# CH32V203C8T6-R0.net
KiCad netlist of a schematic drawn in Altium Designer
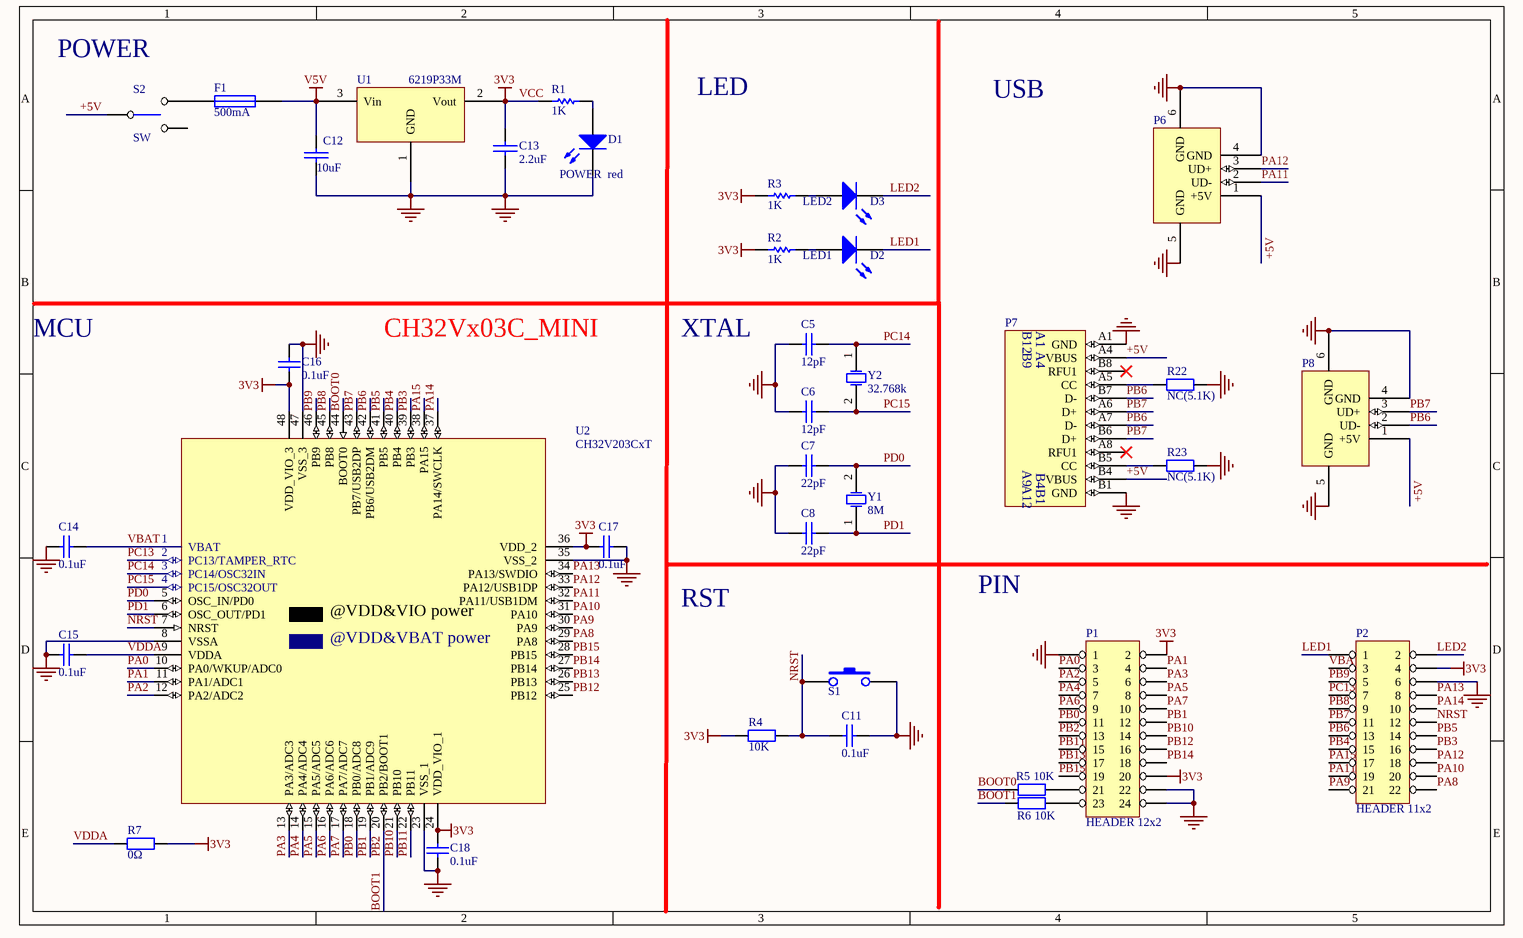
[diagram p0: CH32V203C8T6-R0.SchDoc]

(export (version "E")
  (design (tool "Eeschema 10.0.6"))
  (components
    (comp (ref "C5")
      (value "12pF")
      (footprint "0603_C")
      (description "Capacitor")
      (fields (field (name "PUBLISHER") "Altium Limited"))
      (libsource (lib "*") (part "Cap"))
    )
    (comp (ref "C6")
      (value "12pF")
      (footprint "0603_C")
      (description "Capacitor")
      (fields (field (name "PUBLISHER") "Altium Limited"))
      (libsource (lib "*") (part "Cap"))
    )
    (comp (ref "C7")
      (value "22pF")
      (footprint "0603_C")
      (description "Capacitor")
      (fields (field (name "PUBLISHER") "Altium Limited"))
      (libsource (lib "*") (part "Cap"))
    )
    (comp (ref "C8")
      (value "22pF")
      (footprint "0603_C")
      (description "Capacitor")
      (fields (field (name "PUBLISHER") "Altium Limited"))
      (libsource (lib "*") (part "Cap"))
    )
    (comp (ref "C11")
      (value "0.1uF")
      (footprint "0603_C")
      (description "Capacitor")
      (fields (field (name "PUBLISHER") "Altium Limited"))
      (libsource (lib "*") (part "Cap"))
    )
    (comp (ref "C12")
      (value "10uF")
      (footprint "3216_C")
      (description "Capacitor")
      (libsource (lib "*") (part "CAP"))
    )
    (comp (ref "C13")
      (value "2.2uF")
      (footprint "0603_C")
      (description "Capacitor")
      (libsource (lib "*") (part "CAP"))
    )
    (comp (ref "C14")
      (value "0.1uF")
      (footprint "0603_C")
      (description "Capacitor")
      (fields (field (name "PUBLISHER") "Altium Limited"))
      (libsource (lib "*") (part "Cap"))
    )
    (comp (ref "C15")
      (value "0.1uF")
      (footprint "0603_C")
      (description "Capacitor")
      (fields (field (name "PUBLISHER") "Altium Limited"))
      (libsource (lib "*") (part "Cap"))
    )
    (comp (ref "C16")
      (value "0.1uF")
      (footprint "0603_C")
      (description "Capacitor")
      (fields (field (name "PUBLISHER") "Altium Limited"))
      (libsource (lib "*") (part "Cap"))
    )
    (comp (ref "C17")
      (value "0.1uF")
      (footprint "0603_C")
      (description "Capacitor")
      (fields (field (name "PUBLISHER") "Altium Limited"))
      (libsource (lib "*") (part "Cap"))
    )
    (comp (ref "C18")
      (value "0.1uF")
      (footprint "0603_C")
      (description "Capacitor")
      (fields (field (name "PUBLISHER") "Altium Limited"))
      (libsource (lib "*") (part "Cap"))
    )
    (comp (ref "D1")
      (value "POWER  red")
      (footprint "0603+")
      (description "Typical INFRARED GaAs LED")
      (fields (field (name "PUBLISHER") "Altium Limited"))
      (libsource (lib "*") (part "LED0"))
    )
    (comp (ref "D2")
      (value "LED1")
      (footprint "0603+")
      (description "Typical INFRARED GaAs LED")
      (fields (field (name "PUBLISHER") "Altium Limited"))
      (libsource (lib "*") (part "LED0"))
    )
    (comp (ref "D3")
      (value "LED2")
      (footprint "0603+")
      (description "Typical INFRARED GaAs LED")
      (fields (field (name "PUBLISHER") "Altium Limited"))
      (libsource (lib "*") (part "LED0"))
    )
    (comp (ref "F1")
      (value "500mA")
      (footprint "0603")
      (description "Fuse")
      (libsource (lib "*") (part "FUSE1"))
    )
    (comp (ref "P1")
      (value "HEADER 12x2")
      (footprint "MYPCB:IDC24-2.54MM")
      (description "Header, 12-Pin, Dual row")
      (libsource (lib "wch_sch_others") (part "HEADER 12x2"))
    )
    (comp (ref "P2")
      (value "HEADER 11x2")
      (footprint "MYPCB:IDC22-2.54MM")
      (description "Header, 11-Pin, Dual row")
      (libsource (lib "wch_sch_others") (part "HEADER 11x2"))
    )
    (comp (ref "P6")
      (value "USB_A")
      (footprint "USBAF")
      (description "USB Port")
      (libsource (lib "*") (part "USB"))
    )
    (comp (ref "P7")
      (value "TYPE-C")
      (footprint "TYPE-C-Receptacle-2.0")
      (libsource (lib "*") (part "TYPE-C1"))
    )
    (comp (ref "P8")
      (value "USB_A")
      (footprint "USBAF")
      (description "USB Port")
      (libsource (lib "*") (part "USB"))
    )
    (comp (ref "R1")
      (value "1K")
      (footprint "0603")
      (description "Semiconductor Resistor")
      (fields (field (name "PUBLISHER") "Altium Limited"))
      (libsource (lib "*") (part "Res Semi"))
    )
    (comp (ref "R2")
      (value "1K")
      (footprint "0603")
      (description "Semiconductor Resistor")
      (fields (field (name "PUBLISHER") "Altium Limited"))
      (libsource (lib "*") (part "Res Semi"))
    )
    (comp (ref "R3")
      (value "1K")
      (footprint "0603")
      (description "Semiconductor Resistor")
      (fields (field (name "PUBLISHER") "Altium Limited"))
      (libsource (lib "*") (part "Res Semi"))
    )
    (comp (ref "R4")
      (value "10K")
      (footprint "0603")
      (description "Resistor")
      (fields (field (name "PUBLISHER") "Altium Limited"))
      (libsource (lib "*") (part "Res2"))
    )
    (comp (ref "R5")
      (value "10K")
      (footprint "0603")
      (description "Resistor")
      (fields (field (name "PUBLISHER") "Altium Limited"))
      (libsource (lib "") (part "Res2_1"))
    )
    (comp (ref "R6")
      (value "10K")
      (footprint "0603")
      (description "Resistor")
      (fields (field (name "PUBLISHER") "Altium Limited"))
      (libsource (lib "") (part "Res2_1"))
    )
    (comp (ref "R7")
      (value "0Ω")
      (footprint "0603")
      (description "Resistor")
      (fields (field (name "PUBLISHER") "Altium Limited"))
      (libsource (lib "*") (part "Res2"))
    )
    (comp (ref "R22")
      (value "NC(5.1K)")
      (footprint "0603")
      (description "Resistor")
      (libsource (lib "Miscellaneous Devices") (part "Res2"))
    )
    (comp (ref "R23")
      (value "NC(5.1K)")
      (footprint "0603")
      (description "Resistor")
      (libsource (lib "Miscellaneous Devices") (part "Res2"))
    )
    (comp (ref "S1") (value "KEY") (footprint "贴片按键") (libsource (lib "*") (part "KEY")))
    (comp (ref "S2") (value "SW") (footprint "KEY2") (libsource (lib "*") (part "SW")))
    (comp (ref "U1")
      (value "6219P33M")
      (footprint "SOT-23")
      (libsource (lib "wch_sch_others") (part "6219P33M"))
    )
    (comp (ref "U2")
      (value "CH32V203CxT")
      (footprint "LQFP48")
      (description "RISC-V LMD-MCU, 144MHz, 2*USB FS, CAN")
      (libsource (lib "CHXXX") (part "CH32V203CxT"))
    )
    (comp (ref "Y1")
      (value "8M")
      (footprint "XT_AT49")
      (description "Crystal Oscillator")
      (fields (field (name "PUBLISHER") "Altium Limited"))
      (libsource (lib "*") (part "XTAL"))
    )
    (comp (ref "Y2")
      (value "32.768k")
      (footprint "FC-135")
      (description "Crystal Oscillator")
      (fields (field (name "PUBLISHER") "Altium Limited"))
      (libsource (lib "*") (part "XTAL"))
    )
  )
  (nets
    (net (code "1") (name "/+5V") (class "Default")
      (node (ref "P6") (pin "1") (pinfunction "+5V_1") (pintype "power_in"))
      (node (ref "P7") (pin "A4") (pinfunction "VBUS_A4") (pintype "bidirectional"))
      (node (ref "P7") (pin "B4") (pinfunction "VBUS_B4") (pintype "bidirectional"))
      (node (ref "P8") (pin "1") (pinfunction "+5V_1") (pintype "power_in"))
      (node (ref "S2") (pin "1") (pinfunction "1_1") (pintype "passive"))
    )
    (net (code "3") (name "/BOOT0") (class "Default")
      (node (ref "R5") (pin "1") (pinfunction "1_1") (pintype "passive"))
      (node (ref "U2") (pin "44") (pinfunction "BOOT0_44") (pintype "input"))
    )
    (net (code "4") (name "/BOOT1") (class "Default")
      (node (ref "P1") (pin "13") (pinfunction "13_13") (pintype "passive"))
      (node (ref "R6") (pin "1") (pinfunction "1_1") (pintype "passive"))
      (node (ref "U2") (pin "20") (pinfunction "PB2/BOOT1_20") (pintype "bidirectional"))
    )
    (net (code "5") (name "/LED1") (class "Default")
      (node (ref "D2") (pin "2") (pinfunction "K_2") (pintype "passive"))
      (node (ref "P2") (pin "1") (pinfunction "1_1") (pintype "passive"))
    )
    (net (code "6") (name "/LED2") (class "Default")
      (node (ref "D3") (pin "2") (pinfunction "K_2") (pintype "passive"))
      (node (ref "P2") (pin "2") (pinfunction "2_2") (pintype "passive"))
    )
    (net (code "7") (name "/NRST") (class "Default")
      (node (ref "C11") (pin "2") (pinfunction "2_2") (pintype "passive"))
      (node (ref "P2") (pin "12") (pinfunction "12_12") (pintype "passive"))
      (node (ref "R4") (pin "1") (pinfunction "1_1") (pintype "passive"))
      (node (ref "S1") (pin "1") (pinfunction "1_1") (pintype "passive"))
      (node (ref "U2") (pin "7") (pinfunction "NRST_7") (pintype "input"))
    )
    (net (code "8") (name "/PA0") (class "Default")
      (node (ref "P1") (pin "3") (pinfunction "3_3") (pintype "passive"))
      (node (ref "U2") (pin "10") (pinfunction "PA0/WKUP/ADC0_10") (pintype "bidirectional"))
    )
    (net (code "9") (name "/PA1") (class "Default")
      (node (ref "P1") (pin "4") (pinfunction "4_4") (pintype "passive"))
      (node (ref "U2") (pin "11") (pinfunction "PA1/ADC1_11") (pintype "bidirectional"))
    )
    (net (code "10") (name "/PA2") (class "Default")
      (node (ref "P1") (pin "5") (pinfunction "5_5") (pintype "passive"))
      (node (ref "U2") (pin "12") (pinfunction "PA2/ADC2_12") (pintype "bidirectional"))
    )
    (net (code "11") (name "/PA3") (class "Default")
      (node (ref "P1") (pin "6") (pinfunction "6_6") (pintype "passive"))
      (node (ref "U2") (pin "13") (pinfunction "PA3/ADC3_13") (pintype "bidirectional"))
    )
    (net (code "12") (name "/PA4") (class "Default")
      (node (ref "P1") (pin "7") (pinfunction "7_7") (pintype "passive"))
      (node (ref "U2") (pin "14") (pinfunction "PA4/ADC4_14") (pintype "bidirectional"))
    )
    (net (code "13") (name "/PA5") (class "Default")
      (node (ref "P1") (pin "8") (pinfunction "8_8") (pintype "passive"))
      (node (ref "U2") (pin "15") (pinfunction "PA5/ADC5_15") (pintype "bidirectional"))
    )
    (net (code "14") (name "/PA6") (class "Default")
      (node (ref "P1") (pin "9") (pinfunction "9_9") (pintype "passive"))
      (node (ref "U2") (pin "16") (pinfunction "PA6/ADC6_16") (pintype "bidirectional"))
    )
    (net (code "15") (name "/PA7") (class "Default")
      (node (ref "P1") (pin "10") (pinfunction "10_10") (pintype "passive"))
      (node (ref "U2") (pin "17") (pinfunction "PA7/ADC7_17") (pintype "bidirectional"))
    )
    (net (code "16") (name "/PA8") (class "Default")
      (node (ref "P2") (pin "22") (pinfunction "22_22") (pintype "passive"))
      (node (ref "U2") (pin "29") (pinfunction "PA8_29") (pintype "bidirectional"))
    )
    (net (code "17") (name "/PA9") (class "Default")
      (node (ref "P2") (pin "21") (pinfunction "21_21") (pintype "passive"))
      (node (ref "U2") (pin "30") (pinfunction "PA9_30") (pintype "bidirectional"))
    )
    (net (code "18") (name "/PA10") (class "Default")
      (node (ref "P2") (pin "20") (pinfunction "20_20") (pintype "passive"))
      (node (ref "U2") (pin "31") (pinfunction "PA10_31") (pintype "bidirectional"))
    )
    (net (code "19") (name "/PA11") (class "Default")
      (node (ref "P2") (pin "19") (pinfunction "19_19") (pintype "passive"))
      (node (ref "P6") (pin "2") (pinfunction "UD-_2") (pintype "bidirectional"))
      (node (ref "U2") (pin "32") (pinfunction "PA11/USB1DM_32") (pintype "bidirectional"))
    )
    (net (code "20") (name "/PA12") (class "Default")
      (node (ref "P2") (pin "18") (pinfunction "18_18") (pintype "passive"))
      (node (ref "P6") (pin "3") (pinfunction "UD+_3") (pintype "bidirectional"))
      (node (ref "U2") (pin "33") (pinfunction "PA12/USB1DP_33") (pintype "bidirectional"))
    )
    (net (code "21") (name "/PA13") (class "Default")
      (node (ref "P2") (pin "8") (pinfunction "8_8") (pintype "passive"))
      (node (ref "U2") (pin "34") (pinfunction "PA13/SWDIO_34") (pintype "bidirectional"))
    )
    (net (code "22") (name "/PA14") (class "Default")
      (node (ref "P2") (pin "10") (pinfunction "10_10") (pintype "passive"))
      (node (ref "U2") (pin "37") (pinfunction "PA14/SWCLK_37") (pintype "bidirectional"))
    )
    (net (code "23") (name "/PA15") (class "Default")
      (node (ref "P2") (pin "17") (pinfunction "17_17") (pintype "passive"))
      (node (ref "U2") (pin "38") (pinfunction "PA15_38") (pintype "bidirectional"))
    )
    (net (code "24") (name "/PB0") (class "Default")
      (node (ref "P1") (pin "11") (pinfunction "11_11") (pintype "passive"))
      (node (ref "U2") (pin "18") (pinfunction "PB0/ADC8_18") (pintype "bidirectional"))
    )
    (net (code "25") (name "/PB1") (class "Default")
      (node (ref "P1") (pin "12") (pinfunction "12_12") (pintype "passive"))
      (node (ref "U2") (pin "19") (pinfunction "PB1/ADC9_19") (pintype "bidirectional"))
    )
    (net (code "26") (name "/PB3") (class "Default")
      (node (ref "P2") (pin "16") (pinfunction "16_16") (pintype "passive"))
      (node (ref "U2") (pin "39") (pinfunction "PB3_39") (pintype "bidirectional"))
    )
    (net (code "27") (name "/PB4") (class "Default")
      (node (ref "P2") (pin "15") (pinfunction "15_15") (pintype "passive"))
      (node (ref "U2") (pin "40") (pinfunction "PB4_40") (pintype "bidirectional"))
    )
    (net (code "28") (name "/PB5") (class "Default")
      (node (ref "P2") (pin "14") (pinfunction "14_14") (pintype "passive"))
      (node (ref "U2") (pin "41") (pinfunction "PB5_41") (pintype "bidirectional"))
    )
    (net (code "29") (name "/PB6") (class "Default")
      (node (ref "P2") (pin "13") (pinfunction "13_13") (pintype "passive"))
      (node (ref "P7") (pin "A7") (pinfunction "D-_A7") (pintype "bidirectional"))
      (node (ref "P7") (pin "B7") (pinfunction "D-_B7") (pintype "bidirectional"))
      (node (ref "P8") (pin "2") (pinfunction "UD-_2") (pintype "bidirectional"))
      (node (ref "U2") (pin "42") (pinfunction "PB6/USB2DM_42") (pintype "bidirectional"))
    )
    (net (code "30") (name "/PB7") (class "Default")
      (node (ref "P2") (pin "11") (pinfunction "11_11") (pintype "passive"))
      (node (ref "P7") (pin "A6") (pinfunction "D+_A6") (pintype "bidirectional"))
      (node (ref "P7") (pin "B6") (pinfunction "D+_B6") (pintype "bidirectional"))
      (node (ref "P8") (pin "3") (pinfunction "UD+_3") (pintype "bidirectional"))
      (node (ref "U2") (pin "43") (pinfunction "PB7/USB2DP_43") (pintype "bidirectional"))
    )
    (net (code "31") (name "/PB8") (class "Default")
      (node (ref "P2") (pin "9") (pinfunction "9_9") (pintype "passive"))
      (node (ref "U2") (pin "45") (pinfunction "PB8_45") (pintype "bidirectional"))
    )
    (net (code "32") (name "/PB9") (class "Default")
      (node (ref "P2") (pin "5") (pinfunction "5_5") (pintype "passive"))
      (node (ref "U2") (pin "46") (pinfunction "PB9_46") (pintype "bidirectional"))
    )
    (net (code "33") (name "/PB10") (class "Default")
      (node (ref "P1") (pin "14") (pinfunction "14_14") (pintype "passive"))
      (node (ref "U2") (pin "21") (pinfunction "PB10_21") (pintype "bidirectional"))
    )
    (net (code "34") (name "/PB11") (class "Default")
      (node (ref "P1") (pin "15") (pinfunction "15_15") (pintype "passive"))
      (node (ref "U2") (pin "22") (pinfunction "PB11_22") (pintype "bidirectional"))
    )
    (net (code "35") (name "/PB12") (class "Default")
      (node (ref "P1") (pin "16") (pinfunction "16_16") (pintype "passive"))
      (node (ref "U2") (pin "25") (pinfunction "PB12_25") (pintype "bidirectional"))
    )
    (net (code "36") (name "/PB13") (class "Default")
      (node (ref "P1") (pin "17") (pinfunction "17_17") (pintype "passive"))
      (node (ref "U2") (pin "26") (pinfunction "PB13_26") (pintype "bidirectional"))
    )
    (net (code "37") (name "/PB14") (class "Default")
      (node (ref "P1") (pin "18") (pinfunction "18_18") (pintype "passive"))
      (node (ref "U2") (pin "27") (pinfunction "PB14_27") (pintype "bidirectional"))
    )
    (net (code "38") (name "/PB15") (class "Default")
      (node (ref "P1") (pin "19") (pinfunction "19_19") (pintype "passive"))
      (node (ref "U2") (pin "28") (pinfunction "PB15_28") (pintype "bidirectional"))
    )
    (net (code "39") (name "/PC13") (class "Default")
      (node (ref "P2") (pin "7") (pinfunction "7_7") (pintype "passive"))
      (node (ref "U2") (pin "2") (pinfunction "PC13/TAMPER_RTC_2") (pintype "bidirectional"))
    )
    (net (code "40") (name "/PC14") (class "Default")
      (node (ref "C5") (pin "1") (pinfunction "1_1") (pintype "passive"))
      (node (ref "U2") (pin "3") (pinfunction "PC14/OSC32IN_3") (pintype "bidirectional"))
      (node (ref "Y2") (pin "1") (pinfunction "OSC1_1") (pintype "passive"))
    )
    (net (code "41") (name "/PC15") (class "Default")
      (node (ref "C6") (pin "1") (pinfunction "1_1") (pintype "passive"))
      (node (ref "U2") (pin "4") (pinfunction "PC15/OSC32OUT_4") (pintype "bidirectional"))
      (node (ref "Y2") (pin "2") (pinfunction "OSC2_2") (pintype "passive"))
    )
    (net (code "42") (name "/PD0") (class "Default")
      (node (ref "C7") (pin "2") (pinfunction "2_2") (pintype "passive"))
      (node (ref "U2") (pin "5") (pinfunction "OSC_IN/PD0_5") (pintype "bidirectional"))
      (node (ref "Y1") (pin "2") (pinfunction "OSC2_2") (pintype "passive"))
    )
    (net (code "43") (name "/PD1") (class "Default")
      (node (ref "C8") (pin "2") (pinfunction "2_2") (pintype "passive"))
      (node (ref "U2") (pin "6") (pinfunction "OSC_OUT/PD1_6") (pintype "bidirectional"))
      (node (ref "Y1") (pin "1") (pinfunction "OSC1_1") (pintype "passive"))
    )
    (net (code "44") (name "/VBAT") (class "Default")
      (node (ref "C14") (pin "1") (pinfunction "1_1") (pintype "passive"))
      (node (ref "P2") (pin "3") (pinfunction "3_3") (pintype "passive"))
      (node (ref "U2") (pin "1") (pinfunction "VBAT_1") (pintype "power_in"))
    )
    (net (code "45") (name "/VDDA") (class "Default")
      (node (ref "C15") (pin "1") (pinfunction "1_1") (pintype "passive"))
      (node (ref "R7") (pin "2") (pinfunction "2_2") (pintype "passive"))
      (node (ref "U2") (pin "9") (pinfunction "VDDA_9") (pintype "power_in"))
    )
    (net (code "46") (name "3V3") (class "Default")
      (node (ref "C13") (pin "1") (pinfunction "1_1") (pintype "passive"))
      (node (ref "C16") (pin "2") (pinfunction "2_2") (pintype "passive"))
      (node (ref "C17") (pin "2") (pinfunction "2_2") (pintype "passive"))
      (node (ref "C18") (pin "2") (pinfunction "2_2") (pintype "passive"))
      (node (ref "P1") (pin "2") (pinfunction "2_2") (pintype "passive"))
      (node (ref "P1") (pin "20") (pinfunction "20_20") (pintype "passive"))
      (node (ref "P2") (pin "4") (pinfunction "4_4") (pintype "passive"))
      (node (ref "R1") (pin "2") (pinfunction "2_2") (pintype "passive"))
      (node (ref "R2") (pin "1") (pinfunction "1_1") (pintype "passive"))
      (node (ref "R3") (pin "1") (pinfunction "1_1") (pintype "passive"))
      (node (ref "R4") (pin "2") (pinfunction "2_2") (pintype "passive"))
      (node (ref "R7") (pin "1") (pinfunction "1_1") (pintype "passive"))
      (node (ref "U1") (pin "2") (pinfunction "Vout_2") (pintype "passive"))
      (node (ref "U2") (pin "24") (pinfunction "VDD_VIO_1_24") (pintype "power_in"))
      (node (ref "U2") (pin "36") (pinfunction "VDD_2_36") (pintype "power_in"))
      (node (ref "U2") (pin "48") (pinfunction "VDD_VIO_3_48") (pintype "power_in"))
    )
    (net (code "47") (name "GND") (class "Default")
      (node (ref "C11") (pin "1") (pinfunction "1_1") (pintype "passive"))
      (node (ref "C12") (pin "2") (pinfunction "2_2") (pintype "passive"))
      (node (ref "C13") (pin "2") (pinfunction "2_2") (pintype "passive"))
      (node (ref "C14") (pin "2") (pinfunction "2_2") (pintype "passive"))
      (node (ref "C15") (pin "2") (pinfunction "2_2") (pintype "passive"))
      (node (ref "C16") (pin "1") (pinfunction "1_1") (pintype "passive"))
      (node (ref "C17") (pin "1") (pinfunction "1_1") (pintype "passive"))
      (node (ref "C18") (pin "1") (pinfunction "1_1") (pintype "passive"))
      (node (ref "C5") (pin "2") (pinfunction "2_2") (pintype "passive"))
      (node (ref "C6") (pin "2") (pinfunction "2_2") (pintype "passive"))
      (node (ref "C7") (pin "1") (pinfunction "1_1") (pintype "passive"))
      (node (ref "C8") (pin "1") (pinfunction "1_1") (pintype "passive"))
      (node (ref "D1") (pin "2") (pinfunction "K_2") (pintype "passive"))
      (node (ref "P1") (pin "1") (pinfunction "1_1") (pintype "passive"))
      (node (ref "P1") (pin "22") (pinfunction "22_22") (pintype "passive"))
      (node (ref "P1") (pin "24") (pinfunction "24_24") (pintype "passive"))
      (node (ref "P2") (pin "6") (pinfunction "6_6") (pintype "passive"))
      (node (ref "P6") (pin "4") (pinfunction "GND_4") (pintype "power_in"))
      (node (ref "P6") (pin "5") (pinfunction "GND_5") (pintype "power_in"))
      (node (ref "P6") (pin "6") (pinfunction "GND_6") (pintype "power_in"))
      (node (ref "P7") (pin "A1") (pinfunction "GND_A1") (pintype "bidirectional"))
      (node (ref "P7") (pin "B1") (pinfunction "GND_B1") (pintype "bidirectional"))
      (node (ref "P8") (pin "4") (pinfunction "GND_4") (pintype "power_in"))
      (node (ref "P8") (pin "5") (pinfunction "GND_5") (pintype "power_in"))
      (node (ref "P8") (pin "6") (pinfunction "GND_6") (pintype "power_in"))
      (node (ref "R22") (pin "2") (pinfunction "2_2") (pintype "passive"))
      (node (ref "R23") (pin "2") (pinfunction "2_2") (pintype "passive"))
      (node (ref "S1") (pin "2") (pinfunction "2_2") (pintype "passive"))
      (node (ref "U1") (pin "1") (pinfunction "GND_1") (pintype "passive"))
      (node (ref "U2") (pin "23") (pinfunction "VSS_1_23") (pintype "power_in"))
      (node (ref "U2") (pin "35") (pinfunction "VSS_2_35") (pintype "power_in"))
      (node (ref "U2") (pin "47") (pinfunction "VSS_3_47") (pintype "power_in"))
      (node (ref "U2") (pin "8") (pinfunction "VSSA_8") (pintype "power_in"))
    )
    (net (code "48") (name "Net-(D1-A)") (class "Default")
      (node (ref "D1") (pin "1") (pinfunction "A_1") (pintype "passive"))
      (node (ref "R1") (pin "1") (pinfunction "1_1") (pintype "passive"))
    )
    (net (code "49") (name "Net-(D2-A)") (class "Default")
      (node (ref "D2") (pin "1") (pinfunction "A_1") (pintype "passive"))
      (node (ref "R2") (pin "2") (pinfunction "2_2") (pintype "passive"))
    )
    (net (code "50") (name "Net-(D3-A)") (class "Default")
      (node (ref "D3") (pin "1") (pinfunction "A_1") (pintype "passive"))
      (node (ref "R3") (pin "2") (pinfunction "2_2") (pintype "passive"))
    )
    (net (code "51") (name "Net-(F1-Pad1)") (class "Default")
      (node (ref "F1") (pin "1") (pinfunction "1_1") (pintype "passive"))
      (node (ref "S2") (pin "3") (pinfunction "3_3") (pintype "passive"))
    )
    (net (code "52") (name "Net-(P1-Pad21)") (class "Default")
      (node (ref "P1") (pin "21") (pinfunction "21_21") (pintype "passive"))
      (node (ref "R5") (pin "2") (pinfunction "2_2") (pintype "passive"))
    )
    (net (code "53") (name "Net-(P1-Pad23)") (class "Default")
      (node (ref "P1") (pin "23") (pinfunction "23_23") (pintype "passive"))
      (node (ref "R6") (pin "2") (pinfunction "2_2") (pintype "passive"))
    )
    (net (code "54") (name "Net-(P7-CC-PadA5)") (class "Default")
      (node (ref "P7") (pin "A5") (pinfunction "CC_A5") (pintype "bidirectional"))
      (node (ref "R22") (pin "1") (pinfunction "1_1") (pintype "passive"))
    )
    (net (code "55") (name "Net-(P7-CC-PadB5)") (class "Default")
      (node (ref "P7") (pin "B5") (pinfunction "CC_B5") (pintype "bidirectional"))
      (node (ref "R23") (pin "1") (pinfunction "1_1") (pintype "passive"))
    )
    (net (code "56") (name "V5V") (class "Default")
      (node (ref "C12") (pin "1") (pinfunction "1_1") (pintype "passive"))
      (node (ref "F1") (pin "2") (pinfunction "2_2") (pintype "passive"))
      (node (ref "U1") (pin "3") (pinfunction "Vin_3") (pintype "passive"))
    )
    (net (code "57") (name "unconnected-(P7-RFU1-PadA8)") (class "Default")
      (node (ref "P7") (pin "A8") (pinfunction "RFU1_A8") (pintype "bidirectional+no_connect"))
    )
    (net (code "58") (name "unconnected-(P7-RFU1-PadB8)") (class "Default")
      (node (ref "P7") (pin "B8") (pinfunction "RFU1_B8") (pintype "bidirectional+no_connect"))
    )
    (net (code "59") (name "unconnected-(S2-Pad2)") (class "Default")
      (node (ref "S2") (pin "2") (pinfunction "2_2") (pintype "passive"))
    )
  )
)
